# 1.net
KiCad netlist of a schematic drawn in EasyEDA
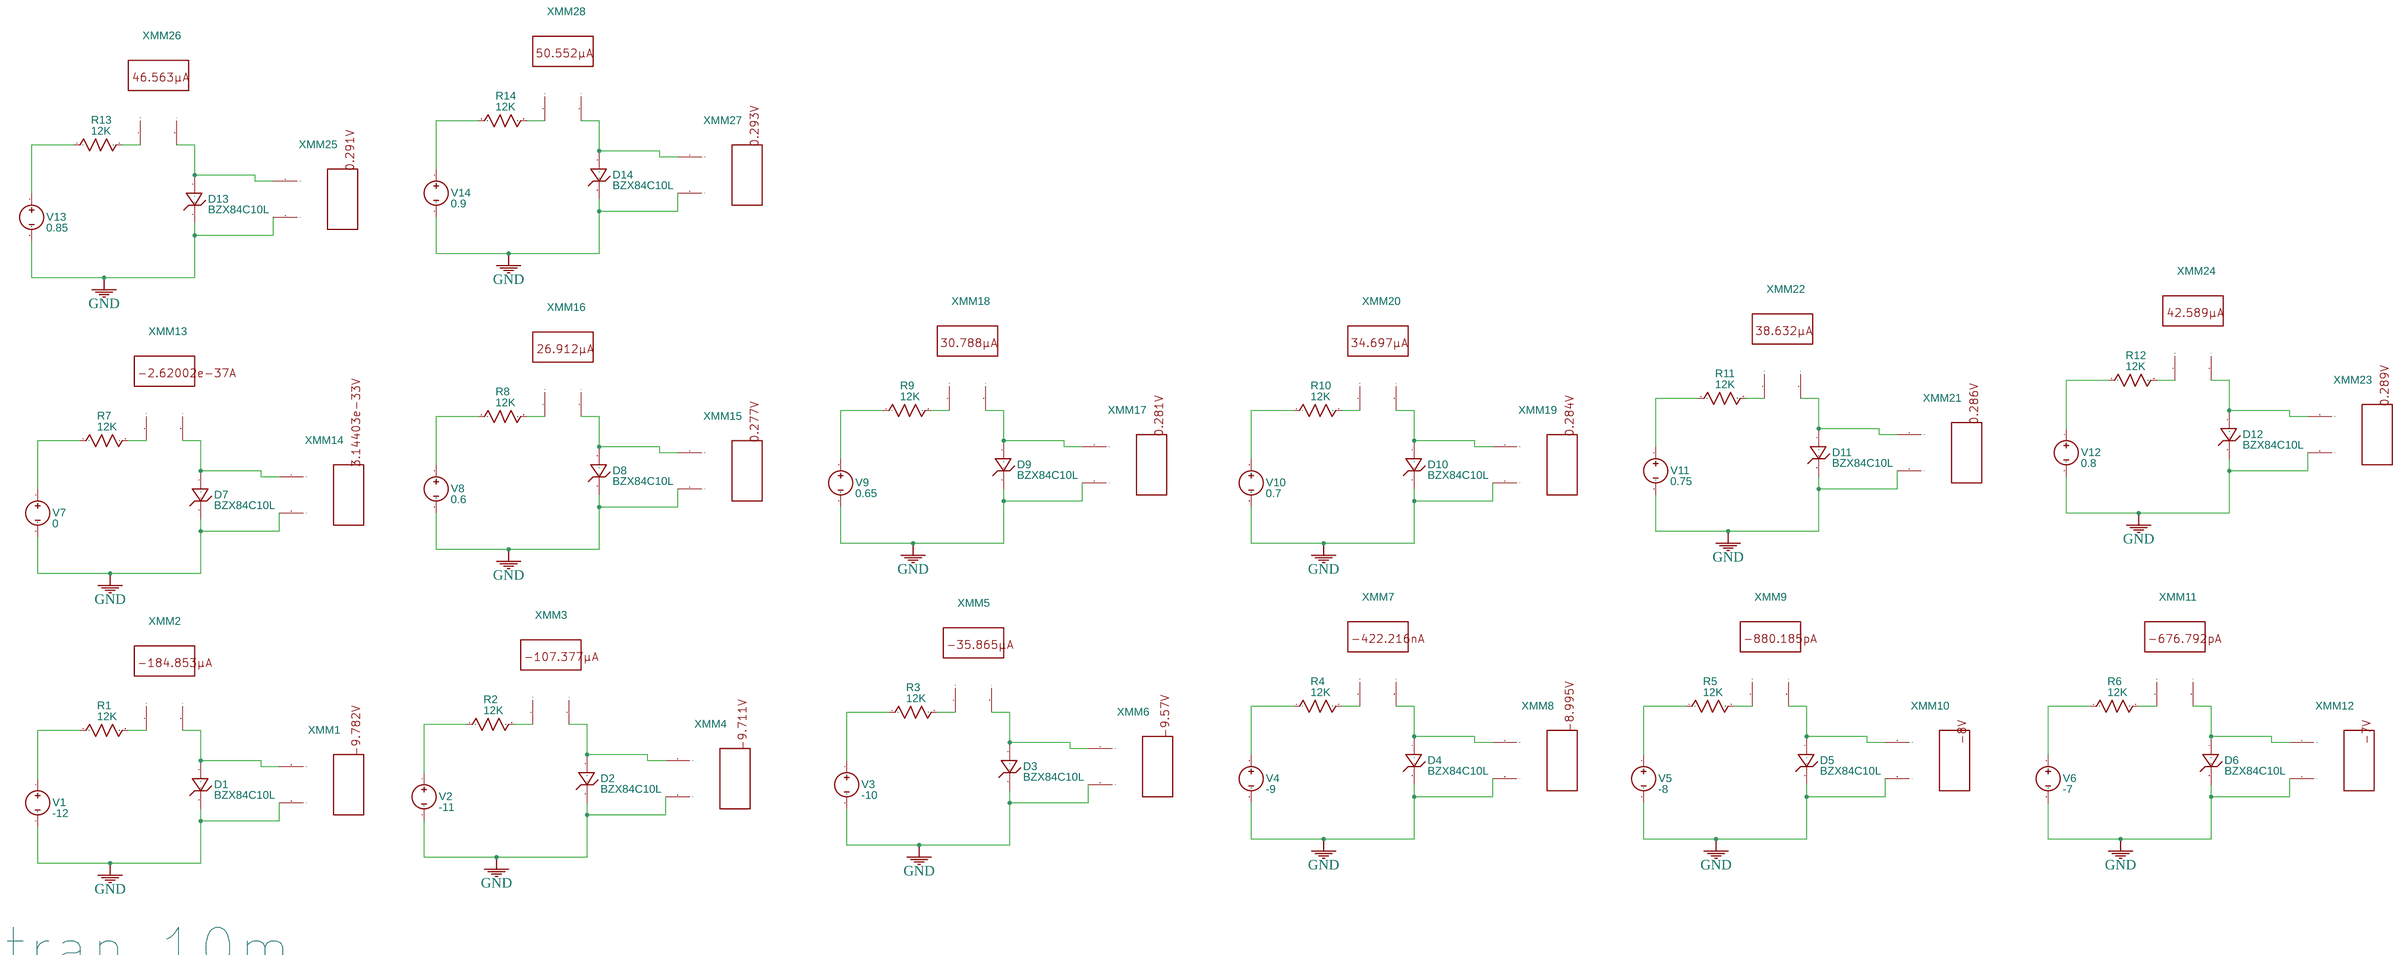
[diagram p0: schematic sheet]

(export (version "E")
  (design (tool "Eeschema 10.0.6"))
  (components
    (comp (ref "D1") (value "BZX84C10L") (libsource (lib "") (part "BZX84C10L")))
    (comp (ref "D2") (value "BZX84C10L") (libsource (lib "") (part "BZX84C10L")))
    (comp (ref "D3") (value "BZX84C10L") (libsource (lib "") (part "BZX84C10L")))
    (comp (ref "D4") (value "BZX84C10L") (libsource (lib "") (part "BZX84C10L")))
    (comp (ref "D5") (value "BZX84C10L") (libsource (lib "") (part "BZX84C10L")))
    (comp (ref "D6") (value "BZX84C10L") (libsource (lib "") (part "BZX84C10L")))
    (comp (ref "D7") (value "BZX84C10L") (libsource (lib "") (part "BZX84C10L")))
    (comp (ref "D8") (value "BZX84C10L") (libsource (lib "") (part "BZX84C10L")))
    (comp (ref "D9") (value "BZX84C10L") (libsource (lib "") (part "BZX84C10L")))
    (comp (ref "D10") (value "BZX84C10L") (libsource (lib "") (part "BZX84C10L")))
    (comp (ref "D11") (value "BZX84C10L") (libsource (lib "") (part "BZX84C10L")))
    (comp (ref "D12") (value "BZX84C10L") (libsource (lib "") (part "BZX84C10L")))
    (comp (ref "D13") (value "BZX84C10L") (libsource (lib "") (part "BZX84C10L")))
    (comp (ref "D14") (value "BZX84C10L") (libsource (lib "") (part "BZX84C10L")))
    (comp (ref "R1") (value "12K") (libsource (lib "") (part "Resistor_US")))
    (comp (ref "R2") (value "12K") (libsource (lib "") (part "Resistor_US")))
    (comp (ref "R3") (value "12K") (libsource (lib "") (part "Resistor_US")))
    (comp (ref "R4") (value "12K") (libsource (lib "") (part "Resistor_US")))
    (comp (ref "R5") (value "12K") (libsource (lib "") (part "Resistor_US")))
    (comp (ref "R6") (value "12K") (libsource (lib "") (part "Resistor_US")))
    (comp (ref "R7") (value "12K") (libsource (lib "") (part "Resistor_US")))
    (comp (ref "R8") (value "12K") (libsource (lib "") (part "Resistor_US")))
    (comp (ref "R9") (value "12K") (libsource (lib "") (part "Resistor_US")))
    (comp (ref "R10") (value "12K") (libsource (lib "") (part "Resistor_US")))
    (comp (ref "R11") (value "12K") (libsource (lib "") (part "Resistor_US")))
    (comp (ref "R12") (value "12K") (libsource (lib "") (part "Resistor_US")))
    (comp (ref "R13") (value "12K") (libsource (lib "") (part "Resistor_US")))
    (comp (ref "R14") (value "12K") (libsource (lib "") (part "Resistor_US")))
    (comp (ref "V1") (value "-12") (libsource (lib "") (part "VDC")))
    (comp (ref "V2") (value "-11") (libsource (lib "") (part "VDC")))
    (comp (ref "V3") (value "-10") (libsource (lib "") (part "VDC")))
    (comp (ref "V4") (value "-9") (libsource (lib "") (part "VDC")))
    (comp (ref "V5") (value "-8") (libsource (lib "") (part "VDC")))
    (comp (ref "V6") (value "-7") (libsource (lib "") (part "VDC")))
    (comp (ref "V7") (value "0") (libsource (lib "") (part "VDC")))
    (comp (ref "V8") (value "0.6") (libsource (lib "") (part "VDC")))
    (comp (ref "V9") (value "0.65") (libsource (lib "") (part "VDC")))
    (comp (ref "V10") (value "0.7") (libsource (lib "") (part "VDC")))
    (comp (ref "V11") (value "0.75") (libsource (lib "") (part "VDC")))
    (comp (ref "V12") (value "0.8") (libsource (lib "") (part "VDC")))
    (comp (ref "V13") (value "0.85") (libsource (lib "") (part "VDC")))
    (comp (ref "V14") (value "0.9") (libsource (lib "") (part "VDC")))
    (comp (ref "XMM1") (value "Multimeter") (libsource (lib "") (part "MULTIMETER_13")))
    (comp (ref "XMM2") (value "Multimeter") (libsource (lib "") (part "MULTIMETER_16")))
    (comp (ref "XMM3") (value "Multimeter") (libsource (lib "") (part "MULTIMETER_17")))
    (comp (ref "XMM4") (value "Multimeter") (libsource (lib "") (part "MULTIMETER_14")))
    (comp (ref "XMM5") (value "Multimeter") (libsource (lib "") (part "MULTIMETER_22")))
    (comp (ref "XMM6") (value "Multimeter") (libsource (lib "") (part "MULTIMETER_10")))
    (comp (ref "XMM7") (value "Multimeter") (libsource (lib "") (part "MULTIMETER_1")))
    (comp (ref "XMM8") (value "Multimeter") (libsource (lib "") (part "MULTIMETER_11")))
    (comp (ref "XMM9") (value "Multimeter") (libsource (lib "") (part "MULTIMETER_23")))
    (comp (ref "XMM10") (value "Multimeter") (libsource (lib "") (part "MULTIMETER_24")))
    (comp (ref "XMM11") (value "Multimeter") (libsource (lib "") (part "MULTIMETER_12")))
    (comp (ref "XMM12") (value "Multimeter") (libsource (lib "") (part "MULTIMETER_25")))
    (comp (ref "XMM13") (value "Multimeter") (libsource (lib "") (part "MULTIMETER_7")))
    (comp (ref "XMM14") (value "Multimeter") (libsource (lib "") (part "MULTIMETER_8")))
    (comp (ref "XMM15") (value "Multimeter") (libsource (lib "") (part "MULTIMETER_27")))
    (comp (ref "XMM16") (value "Multimeter") (libsource (lib "") (part "MULTIMETER_6")))
    (comp (ref "XMM17") (value "Multimeter") (libsource (lib "") (part "MULTIMETER_5")))
    (comp (ref "XMM18") (value "Multimeter") (libsource (lib "") (part "MULTIMETER_4")))
    (comp (ref "XMM19") (value "Multimeter") (libsource (lib "") (part "MULTIMETER")))
    (comp (ref "XMM20") (value "Multimeter") (libsource (lib "") (part "MULTIMETER_21")))
    (comp (ref "XMM21") (value "Multimeter") (libsource (lib "") (part "MULTIMETER_26")))
    (comp (ref "XMM22") (value "Multimeter") (libsource (lib "") (part "MULTIMETER_15")))
    (comp (ref "XMM23") (value "Multimeter") (libsource (lib "") (part "MULTIMETER_2")))
    (comp (ref "XMM24") (value "Multimeter") (libsource (lib "") (part "MULTIMETER_20")))
    (comp (ref "XMM25") (value "Multimeter") (libsource (lib "") (part "MULTIMETER_9")))
    (comp (ref "XMM26") (value "Multimeter") (libsource (lib "") (part "MULTIMETER_19")))
    (comp (ref "XMM27") (value "Multimeter") (libsource (lib "") (part "MULTIMETER_3")))
    (comp (ref "XMM28") (value "Multimeter") (libsource (lib "") (part "MULTIMETER_18")))
  )
  (nets
    (net (code "1") (name "GND") (class "Default")
      (node (ref "D1") (pin "2") (pinfunction "K_2") (pintype "unspecified"))
      (node (ref "D10") (pin "2") (pinfunction "K_2") (pintype "unspecified"))
      (node (ref "D11") (pin "2") (pinfunction "K_2") (pintype "unspecified"))
      (node (ref "D12") (pin "2") (pinfunction "K_2") (pintype "unspecified"))
      (node (ref "D13") (pin "2") (pinfunction "K_2") (pintype "unspecified"))
      (node (ref "D14") (pin "2") (pinfunction "K_2") (pintype "unspecified"))
      (node (ref "D2") (pin "2") (pinfunction "K_2") (pintype "unspecified"))
      (node (ref "D3") (pin "2") (pinfunction "K_2") (pintype "unspecified"))
      (node (ref "D4") (pin "2") (pinfunction "K_2") (pintype "unspecified"))
      (node (ref "D5") (pin "2") (pinfunction "K_2") (pintype "unspecified"))
      (node (ref "D6") (pin "2") (pinfunction "K_2") (pintype "unspecified"))
      (node (ref "D7") (pin "2") (pinfunction "K_2") (pintype "unspecified"))
      (node (ref "D8") (pin "2") (pinfunction "K_2") (pintype "unspecified"))
      (node (ref "D9") (pin "2") (pinfunction "K_2") (pintype "unspecified"))
      (node (ref "V1") (pin "2") (pinfunction "2_2") (pintype "unspecified"))
      (node (ref "V10") (pin "2") (pinfunction "2_2") (pintype "unspecified"))
      (node (ref "V11") (pin "2") (pinfunction "2_2") (pintype "unspecified"))
      (node (ref "V12") (pin "2") (pinfunction "2_2") (pintype "unspecified"))
      (node (ref "V13") (pin "2") (pinfunction "2_2") (pintype "unspecified"))
      (node (ref "V14") (pin "2") (pinfunction "2_2") (pintype "unspecified"))
      (node (ref "V2") (pin "2") (pinfunction "2_2") (pintype "unspecified"))
      (node (ref "V3") (pin "2") (pinfunction "2_2") (pintype "unspecified"))
      (node (ref "V4") (pin "2") (pinfunction "2_2") (pintype "unspecified"))
      (node (ref "V5") (pin "2") (pinfunction "2_2") (pintype "unspecified"))
      (node (ref "V6") (pin "2") (pinfunction "2_2") (pintype "unspecified"))
      (node (ref "V7") (pin "2") (pinfunction "2_2") (pintype "unspecified"))
      (node (ref "V8") (pin "2") (pinfunction "2_2") (pintype "unspecified"))
      (node (ref "V9") (pin "2") (pinfunction "2_2") (pintype "unspecified"))
      (node (ref "XMM1") (pin "2") (pinfunction "I_2") (pintype "unspecified"))
      (node (ref "XMM10") (pin "2") (pinfunction "I_2") (pintype "unspecified"))
      (node (ref "XMM12") (pin "2") (pinfunction "I_2") (pintype "unspecified"))
      (node (ref "XMM14") (pin "2") (pinfunction "I_2") (pintype "unspecified"))
      (node (ref "XMM15") (pin "2") (pinfunction "I_2") (pintype "unspecified"))
      (node (ref "XMM17") (pin "2") (pinfunction "I_2") (pintype "unspecified"))
      (node (ref "XMM19") (pin "2") (pinfunction "I_2") (pintype "unspecified"))
      (node (ref "XMM21") (pin "2") (pinfunction "I_2") (pintype "unspecified"))
      (node (ref "XMM23") (pin "2") (pinfunction "I_2") (pintype "unspecified"))
      (node (ref "XMM25") (pin "2") (pinfunction "I_2") (pintype "unspecified"))
      (node (ref "XMM27") (pin "2") (pinfunction "I_2") (pintype "unspecified"))
      (node (ref "XMM4") (pin "2") (pinfunction "I_2") (pintype "unspecified"))
      (node (ref "XMM6") (pin "2") (pinfunction "I_2") (pintype "unspecified"))
      (node (ref "XMM8") (pin "2") (pinfunction "I_2") (pintype "unspecified"))
    )
    (net (code "2") (name "Net-(D1-A)") (class "Default")
      (node (ref "D1") (pin "1") (pinfunction "A_1") (pintype "unspecified"))
      (node (ref "XMM1") (pin "1") (pinfunction "+_1") (pintype "unspecified"))
      (node (ref "XMM2") (pin "2") (pinfunction "I_2") (pintype "unspecified"))
    )
    (net (code "3") (name "Net-(D2-A)") (class "Default")
      (node (ref "D2") (pin "1") (pinfunction "A_1") (pintype "unspecified"))
      (node (ref "XMM3") (pin "2") (pinfunction "I_2") (pintype "unspecified"))
      (node (ref "XMM4") (pin "1") (pinfunction "+_1") (pintype "unspecified"))
    )
    (net (code "4") (name "Net-(D3-A)") (class "Default")
      (node (ref "D3") (pin "1") (pinfunction "A_1") (pintype "unspecified"))
      (node (ref "XMM5") (pin "2") (pinfunction "I_2") (pintype "unspecified"))
      (node (ref "XMM6") (pin "1") (pinfunction "+_1") (pintype "unspecified"))
    )
    (net (code "5") (name "Net-(D4-A)") (class "Default")
      (node (ref "D4") (pin "1") (pinfunction "A_1") (pintype "unspecified"))
      (node (ref "XMM7") (pin "2") (pinfunction "I_2") (pintype "unspecified"))
      (node (ref "XMM8") (pin "1") (pinfunction "+_1") (pintype "unspecified"))
    )
    (net (code "6") (name "Net-(D5-A)") (class "Default")
      (node (ref "D5") (pin "1") (pinfunction "A_1") (pintype "unspecified"))
      (node (ref "XMM10") (pin "1") (pinfunction "+_1") (pintype "unspecified"))
      (node (ref "XMM9") (pin "2") (pinfunction "I_2") (pintype "unspecified"))
    )
    (net (code "7") (name "Net-(D6-A)") (class "Default")
      (node (ref "D6") (pin "1") (pinfunction "A_1") (pintype "unspecified"))
      (node (ref "XMM11") (pin "2") (pinfunction "I_2") (pintype "unspecified"))
      (node (ref "XMM12") (pin "1") (pinfunction "+_1") (pintype "unspecified"))
    )
    (net (code "8") (name "Net-(D7-A)") (class "Default")
      (node (ref "D7") (pin "1") (pinfunction "A_1") (pintype "unspecified"))
      (node (ref "XMM13") (pin "2") (pinfunction "I_2") (pintype "unspecified"))
      (node (ref "XMM14") (pin "1") (pinfunction "+_1") (pintype "unspecified"))
    )
    (net (code "9") (name "Net-(D8-A)") (class "Default")
      (node (ref "D8") (pin "1") (pinfunction "A_1") (pintype "unspecified"))
      (node (ref "XMM15") (pin "1") (pinfunction "+_1") (pintype "unspecified"))
      (node (ref "XMM16") (pin "2") (pinfunction "I_2") (pintype "unspecified"))
    )
    (net (code "10") (name "Net-(D9-A)") (class "Default")
      (node (ref "D9") (pin "1") (pinfunction "A_1") (pintype "unspecified"))
      (node (ref "XMM17") (pin "1") (pinfunction "+_1") (pintype "unspecified"))
      (node (ref "XMM18") (pin "2") (pinfunction "I_2") (pintype "unspecified"))
    )
    (net (code "11") (name "Net-(D10-A)") (class "Default")
      (node (ref "D10") (pin "1") (pinfunction "A_1") (pintype "unspecified"))
      (node (ref "XMM19") (pin "1") (pinfunction "+_1") (pintype "unspecified"))
      (node (ref "XMM20") (pin "2") (pinfunction "I_2") (pintype "unspecified"))
    )
    (net (code "12") (name "Net-(D11-A)") (class "Default")
      (node (ref "D11") (pin "1") (pinfunction "A_1") (pintype "unspecified"))
      (node (ref "XMM21") (pin "1") (pinfunction "+_1") (pintype "unspecified"))
      (node (ref "XMM22") (pin "2") (pinfunction "I_2") (pintype "unspecified"))
    )
    (net (code "13") (name "Net-(D12-A)") (class "Default")
      (node (ref "D12") (pin "1") (pinfunction "A_1") (pintype "unspecified"))
      (node (ref "XMM23") (pin "1") (pinfunction "+_1") (pintype "unspecified"))
      (node (ref "XMM24") (pin "2") (pinfunction "I_2") (pintype "unspecified"))
    )
    (net (code "14") (name "Net-(D13-A)") (class "Default")
      (node (ref "D13") (pin "1") (pinfunction "A_1") (pintype "unspecified"))
      (node (ref "XMM25") (pin "1") (pinfunction "+_1") (pintype "unspecified"))
      (node (ref "XMM26") (pin "2") (pinfunction "I_2") (pintype "unspecified"))
    )
    (net (code "15") (name "Net-(D14-A)") (class "Default")
      (node (ref "D14") (pin "1") (pinfunction "A_1") (pintype "unspecified"))
      (node (ref "XMM27") (pin "1") (pinfunction "+_1") (pintype "unspecified"))
      (node (ref "XMM28") (pin "2") (pinfunction "I_2") (pintype "unspecified"))
    )
    (net (code "16") (name "Net-(R1-Pad1)") (class "Default")
      (node (ref "R1") (pin "1") (pinfunction "1_1") (pintype "unspecified"))
      (node (ref "V1") (pin "1") (pinfunction "1_1") (pintype "unspecified"))
    )
    (net (code "17") (name "Net-(R2-Pad1)") (class "Default")
      (node (ref "R2") (pin "1") (pinfunction "1_1") (pintype "unspecified"))
      (node (ref "V2") (pin "1") (pinfunction "1_1") (pintype "unspecified"))
    )
    (net (code "18") (name "Net-(R3-Pad1)") (class "Default")
      (node (ref "R3") (pin "1") (pinfunction "1_1") (pintype "unspecified"))
      (node (ref "V3") (pin "1") (pinfunction "1_1") (pintype "unspecified"))
    )
    (net (code "19") (name "Net-(R4-Pad1)") (class "Default")
      (node (ref "R4") (pin "1") (pinfunction "1_1") (pintype "unspecified"))
      (node (ref "V4") (pin "1") (pinfunction "1_1") (pintype "unspecified"))
    )
    (net (code "20") (name "Net-(R5-Pad1)") (class "Default")
      (node (ref "R5") (pin "1") (pinfunction "1_1") (pintype "unspecified"))
      (node (ref "V5") (pin "1") (pinfunction "1_1") (pintype "unspecified"))
    )
    (net (code "21") (name "Net-(R6-Pad1)") (class "Default")
      (node (ref "R6") (pin "1") (pinfunction "1_1") (pintype "unspecified"))
      (node (ref "V6") (pin "1") (pinfunction "1_1") (pintype "unspecified"))
    )
    (net (code "22") (name "Net-(R7-Pad1)") (class "Default")
      (node (ref "R7") (pin "1") (pinfunction "1_1") (pintype "unspecified"))
      (node (ref "V7") (pin "1") (pinfunction "1_1") (pintype "unspecified"))
    )
    (net (code "23") (name "Net-(R8-Pad1)") (class "Default")
      (node (ref "R8") (pin "1") (pinfunction "1_1") (pintype "unspecified"))
      (node (ref "V8") (pin "1") (pinfunction "1_1") (pintype "unspecified"))
    )
    (net (code "24") (name "Net-(R9-Pad1)") (class "Default")
      (node (ref "R9") (pin "1") (pinfunction "1_1") (pintype "unspecified"))
      (node (ref "V9") (pin "1") (pinfunction "1_1") (pintype "unspecified"))
    )
    (net (code "25") (name "Net-(R10-Pad1)") (class "Default")
      (node (ref "R10") (pin "1") (pinfunction "1_1") (pintype "unspecified"))
      (node (ref "V10") (pin "1") (pinfunction "1_1") (pintype "unspecified"))
    )
    (net (code "26") (name "Net-(R11-Pad1)") (class "Default")
      (node (ref "R11") (pin "1") (pinfunction "1_1") (pintype "unspecified"))
      (node (ref "V11") (pin "1") (pinfunction "1_1") (pintype "unspecified"))
    )
    (net (code "27") (name "Net-(R12-Pad1)") (class "Default")
      (node (ref "R12") (pin "1") (pinfunction "1_1") (pintype "unspecified"))
      (node (ref "V12") (pin "1") (pinfunction "1_1") (pintype "unspecified"))
    )
    (net (code "28") (name "Net-(R13-Pad1)") (class "Default")
      (node (ref "R13") (pin "1") (pinfunction "1_1") (pintype "unspecified"))
      (node (ref "V13") (pin "1") (pinfunction "1_1") (pintype "unspecified"))
    )
    (net (code "29") (name "Net-(R14-Pad1)") (class "Default")
      (node (ref "R14") (pin "1") (pinfunction "1_1") (pintype "unspecified"))
      (node (ref "V14") (pin "1") (pinfunction "1_1") (pintype "unspecified"))
    )
    (net (code "30") (name "Net-(XMM2-+)") (class "Default")
      (node (ref "R1") (pin "2") (pinfunction "2_2") (pintype "unspecified"))
      (node (ref "XMM2") (pin "1") (pinfunction "+_1") (pintype "unspecified"))
    )
    (net (code "31") (name "Net-(XMM3-+)") (class "Default")
      (node (ref "R2") (pin "2") (pinfunction "2_2") (pintype "unspecified"))
      (node (ref "XMM3") (pin "1") (pinfunction "+_1") (pintype "unspecified"))
    )
    (net (code "32") (name "Net-(XMM5-+)") (class "Default")
      (node (ref "R3") (pin "2") (pinfunction "2_2") (pintype "unspecified"))
      (node (ref "XMM5") (pin "1") (pinfunction "+_1") (pintype "unspecified"))
    )
    (net (code "33") (name "Net-(XMM7-+)") (class "Default")
      (node (ref "R4") (pin "2") (pinfunction "2_2") (pintype "unspecified"))
      (node (ref "XMM7") (pin "1") (pinfunction "+_1") (pintype "unspecified"))
    )
    (net (code "34") (name "Net-(XMM9-+)") (class "Default")
      (node (ref "R5") (pin "2") (pinfunction "2_2") (pintype "unspecified"))
      (node (ref "XMM9") (pin "1") (pinfunction "+_1") (pintype "unspecified"))
    )
    (net (code "35") (name "Net-(XMM11-+)") (class "Default")
      (node (ref "R6") (pin "2") (pinfunction "2_2") (pintype "unspecified"))
      (node (ref "XMM11") (pin "1") (pinfunction "+_1") (pintype "unspecified"))
    )
    (net (code "36") (name "Net-(XMM13-+)") (class "Default")
      (node (ref "R7") (pin "2") (pinfunction "2_2") (pintype "unspecified"))
      (node (ref "XMM13") (pin "1") (pinfunction "+_1") (pintype "unspecified"))
    )
    (net (code "37") (name "Net-(XMM16-+)") (class "Default")
      (node (ref "R8") (pin "2") (pinfunction "2_2") (pintype "unspecified"))
      (node (ref "XMM16") (pin "1") (pinfunction "+_1") (pintype "unspecified"))
    )
    (net (code "38") (name "Net-(XMM18-+)") (class "Default")
      (node (ref "R9") (pin "2") (pinfunction "2_2") (pintype "unspecified"))
      (node (ref "XMM18") (pin "1") (pinfunction "+_1") (pintype "unspecified"))
    )
    (net (code "39") (name "Net-(XMM20-+)") (class "Default")
      (node (ref "R10") (pin "2") (pinfunction "2_2") (pintype "unspecified"))
      (node (ref "XMM20") (pin "1") (pinfunction "+_1") (pintype "unspecified"))
    )
    (net (code "40") (name "Net-(XMM22-+)") (class "Default")
      (node (ref "R11") (pin "2") (pinfunction "2_2") (pintype "unspecified"))
      (node (ref "XMM22") (pin "1") (pinfunction "+_1") (pintype "unspecified"))
    )
    (net (code "41") (name "Net-(XMM24-+)") (class "Default")
      (node (ref "R12") (pin "2") (pinfunction "2_2") (pintype "unspecified"))
      (node (ref "XMM24") (pin "1") (pinfunction "+_1") (pintype "unspecified"))
    )
    (net (code "42") (name "Net-(XMM26-+)") (class "Default")
      (node (ref "R13") (pin "2") (pinfunction "2_2") (pintype "unspecified"))
      (node (ref "XMM26") (pin "1") (pinfunction "+_1") (pintype "unspecified"))
    )
    (net (code "43") (name "Net-(XMM28-+)") (class "Default")
      (node (ref "R14") (pin "2") (pinfunction "2_2") (pintype "unspecified"))
      (node (ref "XMM28") (pin "1") (pinfunction "+_1") (pintype "unspecified"))
    )
  )
)
